# DIS07050H-V2_0-20231201.net
KiCad netlist of a schematic drawn in EAGLE
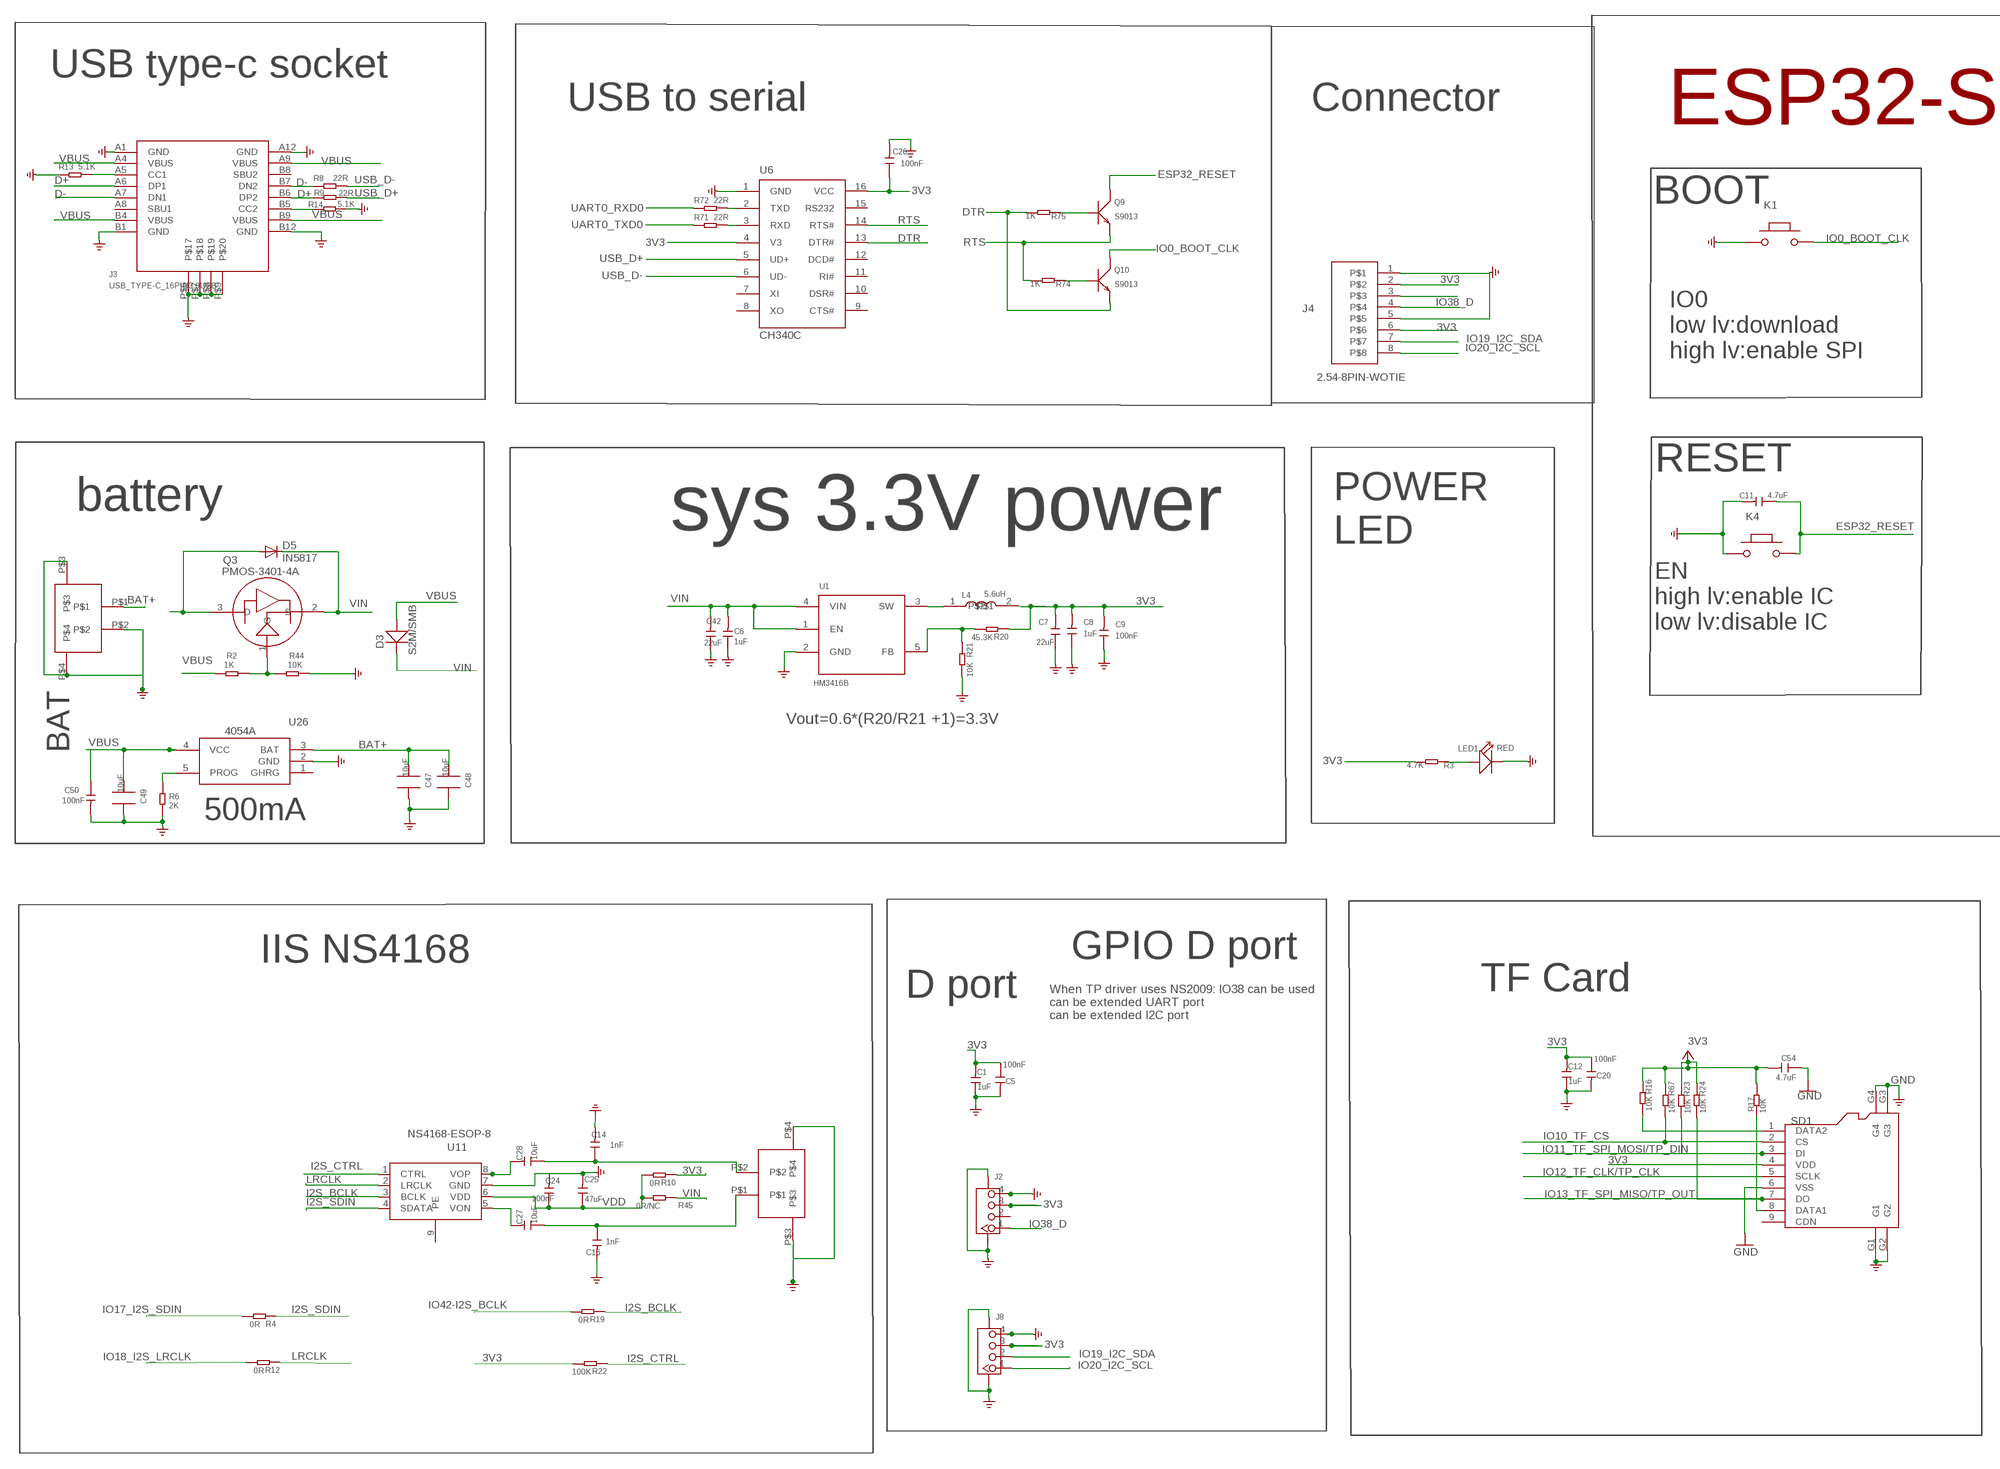
[diagram p0: schematic, sheet 1, part 1 of 2]
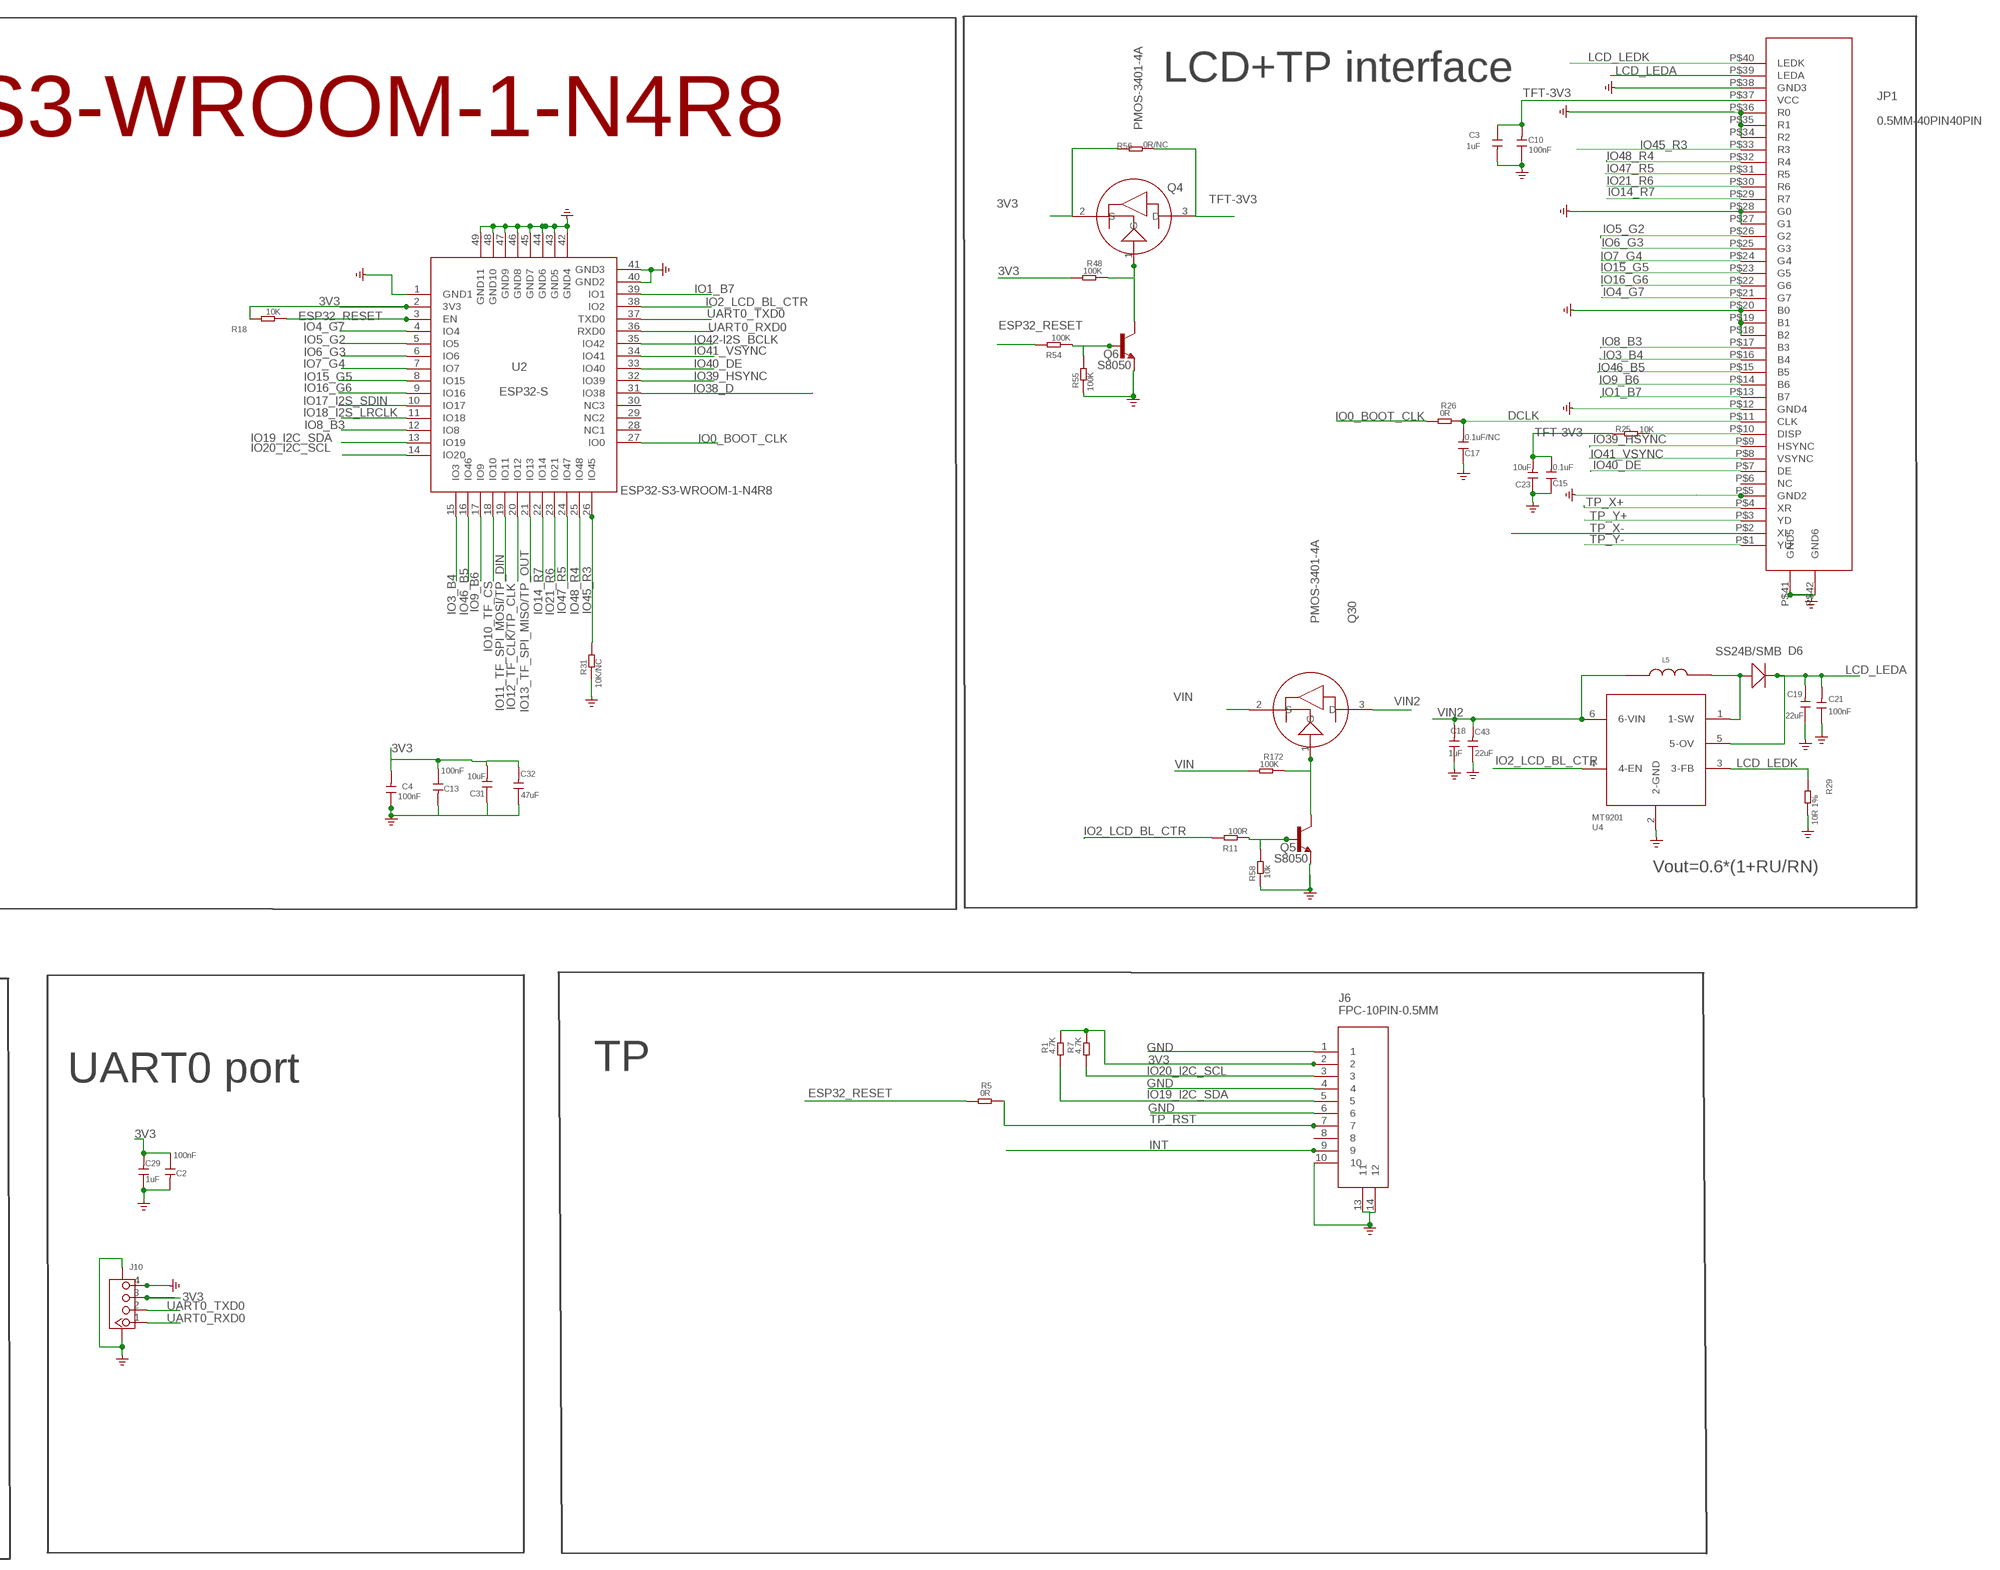
[diagram p1: schematic, sheet 1, part 2 of 2]

(export (version "E")
  (design (tool "Eeschema 10.0.6"))
  (components
    (comp (ref "C1")
      (value "1uF")
      (footprint "eagle-import:DISCRETE_C0603")
      (libsource (lib "eagle-import") (part "A_xbj_DISCRETE_C-0603"))
    )
    (comp (ref "C2")
      (value "100nF")
      (footprint "eagle-import:C0603")
      (libsource (lib "eagle-import") (part "C-0603"))
    )
    (comp (ref "C3")
      (value "1uF")
      (footprint "eagle-import:C0603")
      (libsource (lib "eagle-import") (part "C-0603"))
    )
    (comp (ref "C4")
      (value "100nF")
      (footprint "eagle-import:C0603")
      (libsource (lib "eagle-import") (part "C-0603"))
    )
    (comp (ref "C5")
      (value "100nF")
      (footprint "eagle-import:C0603")
      (libsource (lib "eagle-import") (part "C-0603"))
    )
    (comp (ref "C6")
      (value "1uF")
      (footprint "eagle-import:0603")
      (libsource (lib "eagle-import") (part "C0603"))
    )
    (comp (ref "C7")
      (value "22uF")
      (footprint "eagle-import:0805")
      (libsource (lib "eagle-import") (part "C0805"))
    )
    (comp (ref "C8")
      (value "1uF")
      (footprint "eagle-import:0603")
      (libsource (lib "eagle-import") (part "C0603"))
    )
    (comp (ref "C9")
      (value "100nF")
      (footprint "eagle-import:0603")
      (libsource (lib "eagle-import") (part "C0603"))
    )
    (comp (ref "C10")
      (value "100nF")
      (footprint "eagle-import:C0603")
      (libsource (lib "eagle-import") (part "C-0603"))
    )
    (comp (ref "C11")
      (value "4.7uF")
      (footprint "eagle-import:0603")
      (libsource (lib "eagle-import") (part "C0603"))
    )
    (comp (ref "C12")
      (value "1uF")
      (footprint "eagle-import:DISCRETE_C0603")
      (libsource (lib "eagle-import") (part "A_xbj_DISCRETE_C-0603"))
    )
    (comp (ref "C13")
      (value "100nF")
      (footprint "eagle-import:C0603")
      (libsource (lib "eagle-import") (part "C-0603"))
    )
    (comp (ref "C14")
      (value "1nF")
      (footprint "eagle-import:C0603")
      (libsource (lib "eagle-import") (part "C-0603"))
    )
    (comp (ref "C15")
      (value "0.1uF")
      (footprint "eagle-import:DISCRETE_C0603")
      (libsource (lib "eagle-import") (part "DISCRETE_C-0603"))
    )
    (comp (ref "C16")
      (value "1nF")
      (footprint "eagle-import:C0603")
      (libsource (lib "eagle-import") (part "C-0603"))
    )
    (comp (ref "C17")
      (value "0.1uF/NC")
      (footprint "eagle-import:DISCRETE_C0603")
      (libsource (lib "eagle-import") (part "DISCRETE_C-0603"))
    )
    (comp (ref "C18")
      (value "1uF")
      (footprint "eagle-import:0603")
      (libsource (lib "eagle-import") (part "C0603"))
    )
    (comp (ref "C19")
      (value "22uF")
      (footprint "eagle-import:0805")
      (libsource (lib "eagle-import") (part "C0805"))
    )
    (comp (ref "C20")
      (value "100nF")
      (footprint "eagle-import:C0603")
      (libsource (lib "eagle-import") (part "C-0603"))
    )
    (comp (ref "C21")
      (value "100nF")
      (footprint "eagle-import:0603")
      (libsource (lib "eagle-import") (part "C0603"))
    )
    (comp (ref "C23")
      (value "10uF")
      (footprint "eagle-import:DISCRETE_C0603")
      (libsource (lib "eagle-import") (part "DISCRETE_C-0603"))
    )
    (comp (ref "C24")
      (value "100nF")
      (footprint "eagle-import:C0603")
      (libsource (lib "eagle-import") (part "C-0603"))
    )
    (comp (ref "C25")
      (value "47uF")
      (footprint "eagle-import:0805")
      (libsource (lib "eagle-import") (part "C0805"))
    )
    (comp (ref "C26")
      (value "100nF")
      (footprint "eagle-import:0603")
      (libsource (lib "eagle-import") (part "C0603"))
    )
    (comp (ref "C27")
      (value "10uF")
      (footprint "eagle-import:DISCRETE_C0603")
      (libsource (lib "eagle-import") (part "A_xbj_DISCRETE_C-0603"))
    )
    (comp (ref "C28")
      (value "10uF")
      (footprint "eagle-import:DISCRETE_C0603")
      (libsource (lib "eagle-import") (part "A_xbj_DISCRETE_C-0603"))
    )
    (comp (ref "C29")
      (value "1uF")
      (footprint "eagle-import:DISCRETE_C0603")
      (libsource (lib "eagle-import") (part "A_xbj_DISCRETE_C-0603"))
    )
    (comp (ref "C31")
      (value "10uF")
      (footprint "eagle-import:DISCRETE_C0603")
      (libsource (lib "eagle-import") (part "DISCRETE_C-0603"))
    )
    (comp (ref "C32")
      (value "47uF")
      (footprint "eagle-import:0805")
      (libsource (lib "eagle-import") (part "C0805"))
    )
    (comp (ref "C42")
      (value "22uF")
      (footprint "eagle-import:0805")
      (libsource (lib "eagle-import") (part "C0805"))
    )
    (comp (ref "C43")
      (value "22uF")
      (footprint "eagle-import:0805")
      (libsource (lib "eagle-import") (part "C0805"))
    )
    (comp (ref "C47")
      (value "10uF")
      (footprint "eagle-import:0805_S")
      (libsource (lib "eagle-import") (part "C0805_S"))
    )
    (comp (ref "C48")
      (value "10uF")
      (footprint "eagle-import:0805_S")
      (libsource (lib "eagle-import") (part "C0805_S"))
    )
    (comp (ref "C49")
      (value "10uF")
      (footprint "eagle-import:0805_S")
      (libsource (lib "eagle-import") (part "C0805_S"))
    )
    (comp (ref "C50")
      (value "100nF")
      (footprint "eagle-import:C0603")
      (libsource (lib "eagle-import") (part "C-0603"))
    )
    (comp (ref "C54")
      (value "4.7uF")
      (footprint "eagle-import:DISCRETE_C0603")
      (libsource (lib "eagle-import") (part "DISCRETE_C-0603"))
    )
    (comp (ref "D3")
      (value "S2M/SMB")
      (footprint "eagle-import:214AB")
      (libsource (lib "eagle-import") (part "214ABDO-214AB"))
    )
    (comp (ref "D5")
      (value "IN5817")
      (footprint "eagle-import:DO-214AC")
      (libsource (lib "eagle-import") (part "DIODE-DO-214AC"))
    )
    (comp (ref "D6")
      (value "SS24B/SMB")
      (footprint "eagle-import:214AB")
      (libsource (lib "eagle-import") (part "214ABDO-214AB"))
    )
    (comp (ref "J1")
      (value "PH2.0WT-2PIN")
      (footprint "eagle-import:PH2.0WT-2PIN")
      (libsource (lib "eagle-import") (part "PH2.0WT-2PIN"))
    )
    (comp (ref "J2")
      (value "CONNECTOR_TWIG-4P-2.0-SMD-FEMALE-REINFORCE90D")
      (footprint "eagle-import:CONNECTOR_4P-SMD-2.0-90D")
      (libsource (lib "eagle-import") (part "CONNECTOR_TWIG-4P-2.0-SMD-FEMALE-REINFORCE90D"))
    )
    (comp (ref "J3")
      (value "USB_TYPE-C_16PIN3.0USB")
      (footprint "eagle-import:KEVIN_3.0TYPEC-SMD")
      (libsource (lib "eagle-import") (part "USB_TYPE-C_16PIN3.0USB"))
    )
    (comp (ref "J4")
      (value "2.54-8PIN-WOTIE")
      (footprint "eagle-import:2.54-8P-WOTIE")
      (libsource (lib "eagle-import") (part "2.54-8PIN-WOTIE"))
    )
    (comp (ref "J5")
      (value "PH2.0WT-2PIN")
      (footprint "eagle-import:PH2.0WT-2PIN")
      (libsource (lib "eagle-import") (part "PH2.0WT-2PIN"))
    )
    (comp (ref "J6")
      (value "FPC-10PIN-0.5MM")
      (footprint "eagle-import:FPC-10PIN-0.5MM")
      (libsource (lib "eagle-import") (part "FPC-10PIN-0.5MM"))
    )
    (comp (ref "J8")
      (value "CONNECTOR_TWIG-4P-2.0-SMD-FEMALE-REINFORCE90D")
      (footprint "eagle-import:CONNECTOR_4P-SMD-2.0-90D")
      (libsource (lib "eagle-import") (part "CONNECTOR_TWIG-4P-2.0-SMD-FEMALE-REINFORCE90D"))
    )
    (comp (ref "J10")
      (value "CONNECTOR_TWIG-4P-2.0-SMD-FEMALE-REINFORCE90D")
      (footprint "eagle-import:CONNECTOR_4P-SMD-2.0-90D")
      (libsource (lib "eagle-import") (part "CONNECTOR_TWIG-4P-2.0-SMD-FEMALE-REINFORCE90D"))
    )
    (comp (ref "JP1")
      (value "0.5MM-40PIN40PIN")
      (footprint "eagle-import:0.5MM_40P")
      (libsource (lib "eagle-import") (part "0.5MM-40PIN40PIN"))
    )
    (comp (ref "K1")
      (value "BUTTON")
      (footprint "eagle-import:157SW")
      (libsource (lib "eagle-import") (part "PB157"))
    )
    (comp (ref "K4")
      (value "BUTTON")
      (footprint "eagle-import:157SW")
      (libsource (lib "eagle-import") (part "PB157"))
    )
    (comp (ref "L4")
      (value "5.6uH")
      (footprint "eagle-import:CD54_CD54")
      (libsource (lib "eagle-import") (part "L-0530"))
    )
    (comp (ref "L5")
      (value "CD32_6.8uH")
      (footprint "eagle-import:CD32")
      (libsource (lib "eagle-import") (part "CD32_950MA"))
    )
    (comp (ref "LED1")
      (value "RED")
      (footprint "eagle-import:DISCRETE_LED-0603")
      (libsource (lib "eagle-import") (part "DISCRETE_LED0603"))
    )
    (comp (ref "Q3")
      (value "PMOS-3401-4A")
      (footprint "eagle-import:SOT-23")
      (libsource (lib "eagle-import") (part "P-MOS-SOT23"))
    )
    (comp (ref "Q4")
      (value "PMOS-3401-4A")
      (footprint "eagle-import:SOT-23")
      (libsource (lib "eagle-import") (part "P-MOS-SOT23"))
    )
    (comp (ref "Q5")
      (value "S8050")
      (footprint "eagle-import:SPARKFUN_SOT23")
      (libsource (lib "eagle-import") (part "SPARKFUN_TRANSISTOR_NPNSOT23"))
    )
    (comp (ref "Q6")
      (value "S8050")
      (footprint "eagle-import:SPARKFUN_SOT23")
      (libsource (lib "eagle-import") (part "SPARKFUN_TRANSISTOR_NPNSOT23"))
    )
    (comp (ref "Q9")
      (value "S9013")
      (footprint "eagle-import:SOT23@1")
      (libsource (lib "eagle-import") (part "TRANSISTOR-NPN-SOT23"))
    )
    (comp (ref "Q10")
      (value "S9013")
      (footprint "eagle-import:SOT23@1")
      (libsource (lib "eagle-import") (part "TRANSISTOR-NPN-SOT23"))
    )
    (comp (ref "Q30")
      (value "PMOS-3401-4A")
      (footprint "eagle-import:SOT-23")
      (libsource (lib "eagle-import") (part "P-MOS-SOT23"))
    )
    (comp (ref "R1")
      (value "4.7K")
      (footprint "eagle-import:R0603")
      (libsource (lib "eagle-import") (part "R-0603"))
    )
    (comp (ref "R2")
      (value "1K")
      (footprint "eagle-import:DISCRETE_R0603")
      (libsource (lib "eagle-import") (part "DISCRETE_R-0603"))
    )
    (comp (ref "R3")
      (value "4.7K")
      (footprint "eagle-import:DISCRETE_R0603")
      (libsource (lib "eagle-import") (part "Crowtail-_LED-V2.0-20190615-01_DISCRETE_R-0603"))
    )
    (comp (ref "R4")
      (value "0R")
      (footprint "eagle-import:DISCRETE_R0603")
      (libsource (lib "eagle-import") (part "Crowtail-_LED-V2.0-20190615-01_DISCRETE_R-0603"))
    )
    (comp (ref "R5")
      (value "0R")
      (footprint "eagle-import:R0603")
      (libsource (lib "eagle-import") (part "R-0603"))
    )
    (comp (ref "R6")
      (value "2K")
      (footprint "eagle-import:DISCRETE_R0603")
      (libsource (lib "eagle-import") (part "DISCRETE_R-0603"))
    )
    (comp (ref "R7")
      (value "4.7K")
      (footprint "eagle-import:R0603")
      (libsource (lib "eagle-import") (part "R-0603"))
    )
    (comp (ref "R8")
      (value "22R")
      (footprint "eagle-import:DISCRETE_R0603")
      (libsource (lib "eagle-import") (part "Crowtail-_LED-V2.0-20190615-01_DISCRETE_R-0603"))
    )
    (comp (ref "R9")
      (value "22R")
      (footprint "eagle-import:DISCRETE_R0603")
      (libsource (lib "eagle-import") (part "Crowtail-_LED-V2.0-20190615-01_DISCRETE_R-0603"))
    )
    (comp (ref "R10")
      (value "0R")
      (footprint "eagle-import:DISCRETE_R0603")
      (libsource (lib "eagle-import") (part "Crowtail-_LED-V2.0-20190615-01_DISCRETE_R-0603"))
    )
    (comp (ref "R11")
      (value "100R")
      (footprint "eagle-import:R0603")
      (libsource (lib "eagle-import") (part "R0603"))
    )
    (comp (ref "R12")
      (value "0R")
      (footprint "eagle-import:DISCRETE_R0603")
      (libsource (lib "eagle-import") (part "Crowtail-_LED-V2.0-20190615-01_DISCRETE_R-0603"))
    )
    (comp (ref "R13")
      (value "5.1K")
      (footprint "eagle-import:DISCRETE_R0603")
      (libsource (lib "eagle-import") (part "Crowtail-_LED-V2.0-20190615-01_DISCRETE_R-0603"))
    )
    (comp (ref "R14")
      (value "5.1K")
      (footprint "eagle-import:DISCRETE_R0603")
      (libsource (lib "eagle-import") (part "Crowtail-_LED-V2.0-20190615-01_DISCRETE_R-0603"))
    )
    (comp (ref "R16")
      (value "10K")
      (footprint "eagle-import:DISCRETE_R0603")
      (libsource (lib "eagle-import") (part "Crowtail-_LED-V2.0-20190615-01_DISCRETE_R-0603"))
    )
    (comp (ref "R17")
      (value "10K")
      (footprint "eagle-import:DISCRETE_R0603")
      (libsource (lib "eagle-import") (part "Crowtail-_LED-V2.0-20190615-01_DISCRETE_R-0603"))
    )
    (comp (ref "R18")
      (value "10K")
      (footprint "eagle-import:DISCRETE_R0603")
      (libsource (lib "eagle-import") (part "Crowtail-_LED-V2.0-20190615-01_DISCRETE_R-0603"))
    )
    (comp (ref "R19")
      (value "0R")
      (footprint "eagle-import:DISCRETE_R0603")
      (libsource (lib "eagle-import") (part "Crowtail-_LED-V2.0-20190615-01_DISCRETE_R-0603"))
    )
    (comp (ref "R20")
      (value "45.3K")
      (footprint "eagle-import:DISCRETE_R0603")
      (libsource (lib "eagle-import") (part "Crowtail-_LED-V2.0-20190615-01_DISCRETE_R-0603"))
    )
    (comp (ref "R21")
      (value "10K")
      (footprint "eagle-import:DISCRETE_R0603")
      (libsource (lib "eagle-import") (part "Crowtail-_LED-V2.0-20190615-01_DISCRETE_R-0603"))
    )
    (comp (ref "R22")
      (value "100K")
      (footprint "eagle-import:DISCRETE_R0603")
      (libsource (lib "eagle-import") (part "Crowtail-_LED-V2.0-20190615-01_DISCRETE_R-0603"))
    )
    (comp (ref "R23")
      (value "10K")
      (footprint "eagle-import:DISCRETE_R0603")
      (libsource (lib "eagle-import") (part "Crowtail-_LED-V2.0-20190615-01_DISCRETE_R-0603"))
    )
    (comp (ref "R24")
      (value "10K")
      (footprint "eagle-import:DISCRETE_R0603")
      (libsource (lib "eagle-import") (part "Crowtail-_LED-V2.0-20190615-01_DISCRETE_R-0603"))
    )
    (comp (ref "R25")
      (value "10K")
      (footprint "eagle-import:DISCRETE_R0603")
      (libsource (lib "eagle-import") (part "Crowtail-_LED-V2.0-20190615-01_DISCRETE_R-0603"))
    )
    (comp (ref "R26")
      (value "0R")
      (footprint "eagle-import:R0603")
      (libsource (lib "eagle-import") (part "R-0603"))
    )
    (comp (ref "R29")
      (value "10R 1%")
      (footprint "eagle-import:DISCRETE_R0603")
      (libsource (lib "eagle-import") (part "Crowtail-_LED-V2.0-20190615-01_DISCRETE_R-0603"))
    )
    (comp (ref "R31")
      (value "10K/NC")
      (footprint "eagle-import:R0603")
      (libsource (lib "eagle-import") (part "R0603"))
    )
    (comp (ref "R44")
      (value "10K")
      (footprint "eagle-import:DISCRETE_R0603")
      (libsource (lib "eagle-import") (part "DISCRETE_R-0603"))
    )
    (comp (ref "R45")
      (value "0R/NC")
      (footprint "eagle-import:DISCRETE_R0603")
      (libsource (lib "eagle-import") (part "Crowtail-_LED-V2.0-20190615-01_DISCRETE_R-0603"))
    )
    (comp (ref "R48")
      (value "100K")
      (footprint "eagle-import:R0603")
      (libsource (lib "eagle-import") (part "R-0603"))
    )
    (comp (ref "R54")
      (value "100K")
      (footprint "eagle-import:R0603")
      (libsource (lib "eagle-import") (part "R0603"))
    )
    (comp (ref "R55")
      (value "100K")
      (footprint "eagle-import:R0603")
      (libsource (lib "eagle-import") (part "R0603"))
    )
    (comp (ref "R56")
      (value "0R/NC")
      (footprint "eagle-import:DISCRETE_R0603")
      (libsource (lib "eagle-import") (part "Crowtail-_LED-V2.0-20190615-01_DISCRETE_R-0603"))
    )
    (comp (ref "R58")
      (value "10k")
      (footprint "eagle-import:R0603")
      (libsource (lib "eagle-import") (part "R0603"))
    )
    (comp (ref "R67")
      (value "10K")
      (footprint "eagle-import:DISCRETE_R0603")
      (libsource (lib "eagle-import") (part "Crowtail-_LED-V2.0-20190615-01_DISCRETE_R-0603"))
    )
    (comp (ref "R71")
      (value "22R")
      (footprint "eagle-import:DISCRETE_R0603")
      (libsource (lib "eagle-import") (part "Crowtail-_LED-V2.0-20190615-01_DISCRETE_R-0603"))
    )
    (comp (ref "R72")
      (value "22R")
      (footprint "eagle-import:DISCRETE_R0603")
      (libsource (lib "eagle-import") (part "Crowtail-_LED-V2.0-20190615-01_DISCRETE_R-0603"))
    )
    (comp (ref "R74")
      (value "1K")
      (footprint "eagle-import:DISCRETE_R0603")
      (libsource (lib "eagle-import") (part "Crowtail-_LED-V2.0-20190615-01_DISCRETE_R-0603"))
    )
    (comp (ref "R75")
      (value "1K")
      (footprint "eagle-import:DISCRETE_R0603")
      (libsource (lib "eagle-import") (part "Crowtail-_LED-V2.0-20190615-01_DISCRETE_R-0603"))
    )
    (comp (ref "R172")
      (value "100K")
      (footprint "eagle-import:R0603")
      (libsource (lib "eagle-import") (part "R-0603"))
    )
    (comp (ref "SD1")
      (value "HOLDER-MICROSD-9P")
      (footprint "eagle-import:9P-SMD-W_-RING")
      (libsource (lib "eagle-import") (part "HOLDER-MICROSD-9P"))
    )
    (comp (ref "U1")
      (value "HM3416B")
      (footprint "eagle-import:A_XBJ_SOT23-5")
      (libsource (lib "eagle-import") (part "A_XBJ_HM3420B"))
    )
    (comp (ref "U2")
      (value "ESP32-S")
      (footprint "eagle-import:ESP32-S3")
      (fields (field (name "U2") "ESP32-S3-WROOM-1-N4R8"))
      (libsource (lib "eagle-import") (part "ESP32-S"))
    )
    (comp (ref "U4")
      (value "MT9201")
      (footprint "eagle-import:SOT23-6")
      (libsource (lib "eagle-import") (part "MT9201"))
    )
    (comp (ref "U6")
      (value "CH340C")
      (footprint "eagle-import:SOP-16")
      (libsource (lib "eagle-import") (part "CH340G"))
    )
    (comp (ref "U11")
      (value "NS4168-ESOP-8")
      (footprint "eagle-import:NS4168-ESOP-8")
      (libsource (lib "eagle-import") (part "NS4168-ESOP-8"))
    )
    (comp (ref "U26")
      (value "4054A")
      (footprint "eagle-import:SOP23-5")
      (libsource (lib "eagle-import") (part "4054A"))
    )
  )
  (nets
    (net (code "1") (name "+3V3") (class "Default")
      (node (ref "C1") (pin "2") (pinfunction "2_2") (pintype "passive"))
      (node (ref "C12") (pin "2") (pinfunction "2_2") (pintype "passive"))
      (node (ref "C13") (pin "1") (pinfunction "1_1") (pintype "passive"))
      (node (ref "C2") (pin "1") (pinfunction "1_1") (pintype "passive"))
      (node (ref "C20") (pin "1") (pinfunction "1_1") (pintype "passive"))
      (node (ref "C26") (pin "1") (pinfunction "1_1") (pintype "passive"))
      (node (ref "C29") (pin "2") (pinfunction "2_2") (pintype "passive"))
      (node (ref "C31") (pin "2") (pinfunction "2_2") (pintype "passive"))
      (node (ref "C32") (pin "2") (pinfunction "2_2") (pintype "passive"))
      (node (ref "C4") (pin "2") (pinfunction "2_2") (pintype "passive"))
      (node (ref "C5") (pin "1") (pinfunction "1_1") (pintype "passive"))
      (node (ref "C54") (pin "2") (pinfunction "2_2") (pintype "passive"))
      (node (ref "C7") (pin "2") (pinfunction "2_2") (pintype "passive"))
      (node (ref "C8") (pin "2") (pinfunction "2_2") (pintype "passive"))
      (node (ref "C9") (pin "2") (pinfunction "2_2") (pintype "passive"))
      (node (ref "J10") (pin "3") (pinfunction "3_3") (pintype "bidirectional"))
      (node (ref "J2") (pin "3") (pinfunction "3_3") (pintype "bidirectional"))
      (node (ref "J4") (pin "2") (pinfunction "P$2_2") (pintype "bidirectional"))
      (node (ref "J4") (pin "6") (pinfunction "P$6_6") (pintype "bidirectional"))
      (node (ref "J6") (pin "2") (pinfunction "2_2") (pintype "bidirectional"))
      (node (ref "J8") (pin "3") (pinfunction "3_3") (pintype "bidirectional"))
      (node (ref "L4") (pin "2") (pinfunction "P$2_2") (pintype "bidirectional"))
      (node (ref "Q4") (pin "2") (pinfunction "S_2") (pintype "bidirectional"))
      (node (ref "R1") (pin "2") (pinfunction "2_2") (pintype "passive"))
      (node (ref "R10") (pin "1") (pinfunction "1_1") (pintype "passive"))
      (node (ref "R16") (pin "1") (pinfunction "1_1") (pintype "passive"))
      (node (ref "R17") (pin "1") (pinfunction "1_1") (pintype "passive"))
      (node (ref "R18") (pin "1") (pinfunction "1_1") (pintype "passive"))
      (node (ref "R20") (pin "1") (pinfunction "1_1") (pintype "passive"))
      (node (ref "R22") (pin "2") (pinfunction "2_2") (pintype "passive"))
      (node (ref "R23") (pin "1") (pinfunction "1_1") (pintype "passive"))
      (node (ref "R24") (pin "1") (pinfunction "1_1") (pintype "passive"))
      (node (ref "R3") (pin "2") (pinfunction "2_2") (pintype "passive"))
      (node (ref "R48") (pin "1") (pinfunction "1_1") (pintype "passive"))
      (node (ref "R56") (pin "1") (pinfunction "1_1") (pintype "passive"))
      (node (ref "R67") (pin "1") (pinfunction "1_1") (pintype "passive"))
      (node (ref "R7") (pin "2") (pinfunction "2_2") (pintype "passive"))
      (node (ref "SD1") (pin "4") (pinfunction "VDD_4") (pintype "bidirectional"))
      (node (ref "U2") (pin "2") (pinfunction "3V3_2") (pintype "bidirectional"))
      (node (ref "U6") (pin "16") (pinfunction "VCC_16") (pintype "bidirectional"))
      (node (ref "U6") (pin "4") (pinfunction "V3_4") (pintype "bidirectional"))
    )
    (net (code "2") (name "/BAT+") (class "Default")
      (node (ref "C47") (pin "2") (pinfunction "2_2") (pintype "bidirectional"))
      (node (ref "C48") (pin "2") (pinfunction "2_2") (pintype "bidirectional"))
      (node (ref "D5") (pin "A") (pinfunction "A_A") (pintype "passive"))
      (node (ref "J1") (pin "P$1") (pinfunction "P$1_P$1") (pintype "bidirectional"))
      (node (ref "Q3") (pin "3") (pinfunction "D_3") (pintype "bidirectional"))
      (node (ref "U26") (pin "3") (pinfunction "BAT_3") (pintype "bidirectional"))
    )
    (net (code "3") (name "/D+") (class "Default")
      (node (ref "J3") (pin "A6") (pinfunction "DP1_A6") (pintype "bidirectional"))
      (node (ref "J3") (pin "B6") (pinfunction "DP2_B6") (pintype "bidirectional"))
      (node (ref "R9") (pin "1") (pinfunction "1_1") (pintype "passive"))
    )
    (net (code "4") (name "/D-") (class "Default")
      (node (ref "J3") (pin "A7") (pinfunction "DN1_A7") (pintype "bidirectional"))
      (node (ref "J3") (pin "B7") (pinfunction "DN2_B7") (pintype "bidirectional"))
      (node (ref "R8") (pin "1") (pinfunction "1_1") (pintype "passive"))
    )
    (net (code "5") (name "/DCLK") (class "Default")
      (node (ref "C17") (pin "2") (pinfunction "2_2") (pintype "passive"))
      (node (ref "JP1") (pin "P$11") (pinfunction "CLK_P$11") (pintype "bidirectional"))
      (node (ref "R26") (pin "2") (pinfunction "2_2") (pintype "passive"))
    )
    (net (code "6") (name "/DTR") (class "Default")
      (node (ref "Q10") (pin "2") (pinfunction "E_2") (pintype "passive"))
      (node (ref "R75") (pin "2") (pinfunction "2_2") (pintype "passive"))
      (node (ref "U6") (pin "13") (pinfunction "DTR#_13") (pintype "bidirectional"))
    )
    (net (code "7") (name "/ESP32_RESET") (class "Default")
      (node (ref "C11") (pin "1") (pinfunction "1_1") (pintype "passive"))
      (node (ref "K4") (pin "2") (pinfunction "2_2") (pintype "passive"))
      (node (ref "Q9") (pin "3") (pinfunction "C_3") (pintype "passive"))
      (node (ref "R18") (pin "2") (pinfunction "2_2") (pintype "passive"))
      (node (ref "R5") (pin "1") (pinfunction "1_1") (pintype "passive"))
      (node (ref "R54") (pin "2") (pinfunction "2_2") (pintype "passive"))
      (node (ref "U2") (pin "3") (pinfunction "EN_3") (pintype "bidirectional"))
    )
    (net (code "8") (name "/I2S_BCLK") (class "Default")
      (node (ref "R19") (pin "1") (pinfunction "1_1") (pintype "passive"))
      (node (ref "U11") (pin "3") (pinfunction "BCLK_3") (pintype "bidirectional"))
    )
    (net (code "9") (name "/I2S_CTRL") (class "Default")
      (node (ref "R22") (pin "1") (pinfunction "1_1") (pintype "passive"))
      (node (ref "U11") (pin "1") (pinfunction "CTRL_1") (pintype "bidirectional"))
    )
    (net (code "10") (name "/I2S_SDIN") (class "Default")
      (node (ref "R4") (pin "1") (pinfunction "1_1") (pintype "passive"))
      (node (ref "U11") (pin "4") (pinfunction "SDATA_4") (pintype "bidirectional"))
    )
    (net (code "11") (name "/INT") (class "Default")
      (node (ref "J6") (pin "9") (pinfunction "9_9") (pintype "bidirectional"))
    )
    (net (code "12") (name "/IO0_BOOT_CLK") (class "Default")
      (node (ref "K1") (pin "2") (pinfunction "2_2") (pintype "passive"))
      (node (ref "Q10") (pin "3") (pinfunction "C_3") (pintype "passive"))
      (node (ref "R26") (pin "1") (pinfunction "1_1") (pintype "passive"))
      (node (ref "U2") (pin "27") (pinfunction "IO0_27") (pintype "bidirectional"))
    )
    (net (code "13") (name "/IO1_B7") (class "Default")
      (node (ref "JP1") (pin "P$13") (pinfunction "B7_P$13") (pintype "bidirectional"))
      (node (ref "U2") (pin "39") (pinfunction "IO1_39") (pintype "bidirectional"))
    )
    (net (code "14") (name "/IO2_LCD_BL_CTR") (class "Default")
      (node (ref "R11") (pin "2") (pinfunction "2_2") (pintype "passive"))
      (node (ref "U2") (pin "38") (pinfunction "IO2_38") (pintype "bidirectional"))
      (node (ref "U4") (pin "4") (pinfunction "4-EN_4") (pintype "bidirectional"))
    )
    (net (code "15") (name "/IO3_B4") (class "Default")
      (node (ref "JP1") (pin "P$16") (pinfunction "B4_P$16") (pintype "bidirectional"))
      (node (ref "U2") (pin "15") (pinfunction "IO3_15") (pintype "bidirectional"))
    )
    (net (code "16") (name "/IO4_G7") (class "Default")
      (node (ref "JP1") (pin "P$21") (pinfunction "G7_P$21") (pintype "bidirectional"))
      (node (ref "U2") (pin "4") (pinfunction "IO4_4") (pintype "bidirectional"))
    )
    (net (code "17") (name "/IO5_G2") (class "Default")
      (node (ref "JP1") (pin "P$26") (pinfunction "G2_P$26") (pintype "bidirectional"))
      (node (ref "U2") (pin "5") (pinfunction "IO5_5") (pintype "bidirectional"))
    )
    (net (code "18") (name "/IO6_G3") (class "Default")
      (node (ref "JP1") (pin "P$25") (pinfunction "G3_P$25") (pintype "bidirectional"))
      (node (ref "U2") (pin "6") (pinfunction "IO6_6") (pintype "bidirectional"))
    )
    (net (code "19") (name "/IO7_G4") (class "Default")
      (node (ref "JP1") (pin "P$24") (pinfunction "G4_P$24") (pintype "bidirectional"))
      (node (ref "U2") (pin "7") (pinfunction "IO7_7") (pintype "bidirectional"))
    )
    (net (code "20") (name "/IO8_B3") (class "Default")
      (node (ref "JP1") (pin "P$17") (pinfunction "B3_P$17") (pintype "bidirectional"))
      (node (ref "U2") (pin "12") (pinfunction "IO8_12") (pintype "bidirectional"))
    )
    (net (code "21") (name "/IO9_B6") (class "Default")
      (node (ref "JP1") (pin "P$14") (pinfunction "B6_P$14") (pintype "bidirectional"))
      (node (ref "U2") (pin "17") (pinfunction "IO9_17") (pintype "bidirectional"))
    )
    (net (code "22") (name "/IO10_TF_CS") (class "Default")
      (node (ref "R67") (pin "2") (pinfunction "2_2") (pintype "passive"))
      (node (ref "SD1") (pin "2") (pinfunction "CS_2") (pintype "bidirectional"))
      (node (ref "U2") (pin "18") (pinfunction "IO10_18") (pintype "bidirectional"))
    )
    (net (code "23") (name "/IO11_TF_SPI_MOSI{slash}TP_DIN") (class "Default")
      (node (ref "R23") (pin "2") (pinfunction "2_2") (pintype "passive"))
      (node (ref "SD1") (pin "3") (pinfunction "DI_3") (pintype "bidirectional"))
      (node (ref "U2") (pin "19") (pinfunction "IO11_19") (pintype "bidirectional"))
    )
    (net (code "24") (name "/IO12_TF_CLK{slash}TP_CLK") (class "Default")
      (node (ref "SD1") (pin "5") (pinfunction "SCLK_5") (pintype "bidirectional"))
      (node (ref "U2") (pin "20") (pinfunction "IO12_20") (pintype "bidirectional"))
    )
    (net (code "25") (name "/IO13_TF_SPI_MISO{slash}TP_OUT") (class "Default")
      (node (ref "R24") (pin "2") (pinfunction "2_2") (pintype "passive"))
      (node (ref "SD1") (pin "7") (pinfunction "DO_7") (pintype "bidirectional"))
      (node (ref "U2") (pin "21") (pinfunction "IO13_21") (pintype "bidirectional"))
    )
    (net (code "26") (name "/IO14_R7") (class "Default")
      (node (ref "JP1") (pin "P$29") (pinfunction "R7_P$29") (pintype "bidirectional"))
      (node (ref "U2") (pin "22") (pinfunction "IO14_22") (pintype "bidirectional"))
    )
    (net (code "27") (name "/IO15_G5") (class "Default")
      (node (ref "JP1") (pin "P$23") (pinfunction "G5_P$23") (pintype "bidirectional"))
      (node (ref "U2") (pin "8") (pinfunction "IO15_8") (pintype "bidirectional"))
    )
    (net (code "28") (name "/IO16_G6") (class "Default")
      (node (ref "JP1") (pin "P$22") (pinfunction "G6_P$22") (pintype "bidirectional"))
      (node (ref "U2") (pin "9") (pinfunction "IO16_9") (pintype "bidirectional"))
    )
    (net (code "29") (name "/IO17_I2S_SDIN") (class "Default")
      (node (ref "R4") (pin "2") (pinfunction "2_2") (pintype "passive"))
      (node (ref "U2") (pin "10") (pinfunction "IO17_10") (pintype "bidirectional"))
    )
    (net (code "30") (name "/IO18_I2S_LRCLK") (class "Default")
      (node (ref "R12") (pin "2") (pinfunction "2_2") (pintype "passive"))
      (node (ref "U2") (pin "11") (pinfunction "IO18_11") (pintype "bidirectional"))
    )
    (net (code "31") (name "/IO19_I2C_SDA") (class "Default")
      (node (ref "J4") (pin "7") (pinfunction "P$7_7") (pintype "bidirectional"))
      (node (ref "J6") (pin "5") (pinfunction "5_5") (pintype "bidirectional"))
      (node (ref "J8") (pin "2") (pinfunction "2_2") (pintype "bidirectional"))
      (node (ref "R1") (pin "1") (pinfunction "1_1") (pintype "passive"))
      (node (ref "U2") (pin "13") (pinfunction "IO19_13") (pintype "bidirectional"))
    )
    (net (code "32") (name "/IO20_I2C_SCL") (class "Default")
      (node (ref "J4") (pin "8") (pinfunction "P$8_8") (pintype "bidirectional"))
      (node (ref "J6") (pin "3") (pinfunction "3_3") (pintype "bidirectional"))
      (node (ref "J8") (pin "1") (pinfunction "1_1") (pintype "bidirectional"))
      (node (ref "R7") (pin "1") (pinfunction "1_1") (pintype "passive"))
      (node (ref "U2") (pin "14") (pinfunction "IO20_14") (pintype "bidirectional"))
    )
    (net (code "33") (name "/IO21_R6") (class "Default")
      (node (ref "JP1") (pin "P$30") (pinfunction "R6_P$30") (pintype "bidirectional"))
      (node (ref "U2") (pin "23") (pinfunction "IO21_23") (pintype "bidirectional"))
    )
    (net (code "34") (name "/IO38_D") (class "Default")
      (node (ref "J2") (pin "1") (pinfunction "1_1") (pintype "bidirectional"))
      (node (ref "J4") (pin "4") (pinfunction "P$4_4") (pintype "bidirectional"))
      (node (ref "U2") (pin "31") (pinfunction "IO38_31") (pintype "bidirectional"))
    )
    (net (code "35") (name "/IO39_HSYNC") (class "Default")
      (node (ref "JP1") (pin "P$9") (pinfunction "HSYNC_P$9") (pintype "bidirectional"))
      (node (ref "U2") (pin "32") (pinfunction "IO39_32") (pintype "bidirectional"))
    )
    (net (code "36") (name "/IO40_DE") (class "Default")
      (node (ref "JP1") (pin "P$7") (pinfunction "DE_P$7") (pintype "bidirectional"))
      (node (ref "U2") (pin "33") (pinfunction "IO40_33") (pintype "bidirectional"))
    )
    (net (code "37") (name "/IO41_VSYNC") (class "Default")
      (node (ref "JP1") (pin "P$8") (pinfunction "VSYNC_P$8") (pintype "bidirectional"))
      (node (ref "U2") (pin "34") (pinfunction "IO41_34") (pintype "bidirectional"))
    )
    (net (code "38") (name "/IO42-I2S_BCLK") (class "Default")
      (node (ref "R19") (pin "2") (pinfunction "2_2") (pintype "passive"))
      (node (ref "U2") (pin "35") (pinfunction "IO42_35") (pintype "bidirectional"))
    )
    (net (code "39") (name "/IO45_R3") (class "Default")
      (node (ref "JP1") (pin "P$33") (pinfunction "R3_P$33") (pintype "bidirectional"))
      (node (ref "R31") (pin "2") (pinfunction "2_2") (pintype "passive"))
      (node (ref "U2") (pin "26") (pinfunction "IO45_26") (pintype "bidirectional"))
    )
    (net (code "40") (name "/IO46_B5") (class "Default")
      (node (ref "JP1") (pin "P$15") (pinfunction "B5_P$15") (pintype "bidirectional"))
      (node (ref "U2") (pin "16") (pinfunction "IO46_16") (pintype "bidirectional"))
    )
    (net (code "41") (name "/IO47_R5") (class "Default")
      (node (ref "JP1") (pin "P$31") (pinfunction "R5_P$31") (pintype "bidirectional"))
      (node (ref "U2") (pin "24") (pinfunction "IO47_24") (pintype "bidirectional"))
    )
    (net (code "42") (name "/IO48_R4") (class "Default")
      (node (ref "JP1") (pin "P$32") (pinfunction "R4_P$32") (pintype "bidirectional"))
      (node (ref "U2") (pin "25") (pinfunction "IO48_25") (pintype "bidirectional"))
    )
    (net (code "43") (name "/LCD_LEDA") (class "Default")
      (node (ref "C19") (pin "2") (pinfunction "2_2") (pintype "passive"))
      (node (ref "C21") (pin "2") (pinfunction "2_2") (pintype "passive"))
      (node (ref "D6") (pin "2") (pinfunction "-_2") (pintype "passive"))
      (node (ref "JP1") (pin "P$39") (pinfunction "LEDA_P$39") (pintype "bidirectional"))
      (node (ref "U4") (pin "5") (pinfunction "5-OV_5") (pintype "bidirectional"))
    )
    (net (code "44") (name "/LCD_LEDK") (class "Default")
      (node (ref "JP1") (pin "P$40") (pinfunction "LEDK_P$40") (pintype "bidirectional"))
      (node (ref "R29") (pin "1") (pinfunction "1_1") (pintype "passive"))
      (node (ref "U4") (pin "3") (pinfunction "3-FB_3") (pintype "bidirectional"))
    )
    (net (code "45") (name "/LRCLK") (class "Default")
      (node (ref "R12") (pin "1") (pinfunction "1_1") (pintype "passive"))
      (node (ref "U11") (pin "2") (pinfunction "LRCLK_2") (pintype "bidirectional"))
    )
    (net (code "46") (name "/RTS") (class "Default")
      (node (ref "Q9") (pin "2") (pinfunction "E_2") (pintype "passive"))
      (node (ref "R74") (pin "2") (pinfunction "2_2") (pintype "passive"))
      (node (ref "U6") (pin "14") (pinfunction "RTS#_14") (pintype "bidirectional"))
    )
    (net (code "47") (name "/TFT-3V3") (class "Default")
      (node (ref "C10") (pin "2") (pinfunction "2_2") (pintype "passive"))
      (node (ref "C15") (pin "2") (pinfunction "2_2") (pintype "passive"))
      (node (ref "C23") (pin "2") (pinfunction "2_2") (pintype "passive"))
      (node (ref "C3") (pin "1") (pinfunction "1_1") (pintype "passive"))
      (node (ref "JP1") (pin "P$37") (pinfunction "VCC_P$37") (pintype "bidirectional"))
      (node (ref "Q4") (pin "3") (pinfunction "D_3") (pintype "bidirectional"))
      (node (ref "R25") (pin "1") (pinfunction "1_1") (pintype "passive"))
      (node (ref "R56") (pin "2") (pinfunction "2_2") (pintype "passive"))
    )
    (net (code "48") (name "/TP_RST") (class "Default")
      (node (ref "J6") (pin "7") (pinfunction "7_7") (pintype "bidirectional"))
      (node (ref "R5") (pin "2") (pinfunction "2_2") (pintype "passive"))
    )
    (net (code "49") (name "/TP_X+") (class "Default")
      (node (ref "JP1") (pin "P$4") (pinfunction "XR_P$4") (pintype "bidirectional"))
    )
    (net (code "50") (name "/TP_X-") (class "Default")
      (node (ref "JP1") (pin "P$2") (pinfunction "XL_P$2") (pintype "bidirectional"))
    )
    (net (code "51") (name "/TP_Y+") (class "Default")
      (node (ref "JP1") (pin "P$3") (pinfunction "YD_P$3") (pintype "bidirectional"))
    )
    (net (code "52") (name "/TP_Y-") (class "Default")
      (node (ref "JP1") (pin "P$1") (pinfunction "YU_P$1") (pintype "bidirectional"))
    )
    (net (code "53") (name "/UART0_RXD0") (class "Default")
      (node (ref "J10") (pin "1") (pinfunction "1_1") (pintype "bidirectional"))
      (node (ref "R72") (pin "1") (pinfunction "1_1") (pintype "passive"))
      (node (ref "U2") (pin "36") (pinfunction "RXD0_36") (pintype "bidirectional"))
    )
    (net (code "54") (name "/UART0_TXD0") (class "Default")
      (node (ref "J10") (pin "2") (pinfunction "2_2") (pintype "bidirectional"))
      (node (ref "R71") (pin "1") (pinfunction "1_1") (pintype "passive"))
      (node (ref "U2") (pin "37") (pinfunction "TXD0_37") (pintype "bidirectional"))
    )
    (net (code "55") (name "/USB_D+") (class "Default")
      (node (ref "R9") (pin "2") (pinfunction "2_2") (pintype "passive"))
      (node (ref "U6") (pin "5") (pinfunction "UD+_5") (pintype "bidirectional"))
    )
    (net (code "56") (name "/USB_D-") (class "Default")
      (node (ref "R8") (pin "2") (pinfunction "2_2") (pintype "passive"))
      (node (ref "U6") (pin "6") (pinfunction "UD-_6") (pintype "bidirectional"))
    )
    (net (code "57") (name "/VBUS") (class "Default")
      (node (ref "C49") (pin "2") (pinfunction "2_2") (pintype "bidirectional"))
      (node (ref "C50") (pin "1") (pinfunction "1_1") (pintype "passive"))
      (node (ref "D3") (pin "1") (pinfunction "+_1") (pintype "passive"))
      (node (ref "J3") (pin "A4") (pinfunction "VBUS_A4") (pintype "bidirectional"))
      (node (ref "J3") (pin "A9") (pinfunction "VBUS_A9") (pintype "bidirectional"))
      (node (ref "J3") (pin "B4") (pinfunction "VBUS_B4") (pintype "bidirectional"))
      (node (ref "J3") (pin "B9") (pinfunction "VBUS_B9") (pintype "bidirectional"))
      (node (ref "R2") (pin "2") (pinfunction "2_2") (pintype "passive"))
      (node (ref "U26") (pin "4") (pinfunction "VCC_4") (pintype "bidirectional"))
    )
    (net (code "58") (name "/VDD") (class "Default")
      (node (ref "C24") (pin "1") (pinfunction "1_1") (pintype "passive"))
      (node (ref "C25") (pin "1") (pinfunction "1_1") (pintype "passive"))
      (node (ref "R10") (pin "2") (pinfunction "2_2") (pintype "passive"))
      (node (ref "R45") (pin "2") (pinfunction "2_2") (pintype "passive"))
      (node (ref "U11") (pin "6") (pinfunction "VDD_6") (pintype "bidirectional"))
    )
    (net (code "59") (name "/VIN") (class "Default")
      (node (ref "C42") (pin "2") (pinfunction "2_2") (pintype "passive"))
      (node (ref "C6") (pin "2") (pinfunction "2_2") (pintype "passive"))
      (node (ref "D3") (pin "2") (pinfunction "-_2") (pintype "passive"))
      (node (ref "D5") (pin "C") (pinfunction "C_C") (pintype "passive"))
      (node (ref "Q3") (pin "2") (pinfunction "S_2") (pintype "bidirectional"))
      (node (ref "Q30") (pin "2") (pinfunction "S_2") (pintype "bidirectional"))
      (node (ref "R172") (pin "1") (pinfunction "1_1") (pintype "passive"))
      (node (ref "R45") (pin "1") (pinfunction "1_1") (pintype "passive"))
      (node (ref "U1") (pin "1") (pinfunction "EN_1") (pintype "bidirectional"))
      (node (ref "U1") (pin "4") (pinfunction "VIN_4") (pintype "bidirectional"))
    )
    (net (code "60") (name "/VIN2") (class "Default")
      (node (ref "C18") (pin "2") (pinfunction "2_2") (pintype "passive"))
      (node (ref "C43") (pin "2") (pinfunction "2_2") (pintype "passive"))
      (node (ref "L5") (pin "1") (pinfunction "1_1") (pintype "bidirectional"))
      (node (ref "Q30") (pin "3") (pinfunction "D_3") (pintype "bidirectional"))
      (node (ref "U4") (pin "6") (pinfunction "6-VIN_6") (pintype "bidirectional"))
    )
    (net (code "61") (name "GND") (class "Default")
      (node (ref "C1") (pin "1") (pinfunction "1_1") (pintype "passive"))
      (node (ref "C10") (pin "1") (pinfunction "1_1") (pintype "passive"))
      (node (ref "C11") (pin "2") (pinfunction "2_2") (pintype "passive"))
      (node (ref "C12") (pin "1") (pinfunction "1_1") (pintype "passive"))
      (node (ref "C13") (pin "2") (pinfunction "2_2") (pintype "passive"))
      (node (ref "C14") (pin "2") (pinfunction "2_2") (pintype "passive"))
      (node (ref "C15") (pin "1") (pinfunction "1_1") (pintype "passive"))
      (node (ref "C16") (pin "2") (pinfunction "2_2") (pintype "passive"))
      (node (ref "C17") (pin "1") (pinfunction "1_1") (pintype "passive"))
      (node (ref "C18") (pin "1") (pinfunction "1_1") (pintype "passive"))
      (node (ref "C19") (pin "1") (pinfunction "1_1") (pintype "passive"))
      (node (ref "C2") (pin "2") (pinfunction "2_2") (pintype "passive"))
      (node (ref "C20") (pin "2") (pinfunction "2_2") (pintype "passive"))
      (node (ref "C21") (pin "1") (pinfunction "1_1") (pintype "passive"))
      (node (ref "C23") (pin "1") (pinfunction "1_1") (pintype "passive"))
      (node (ref "C24") (pin "2") (pinfunction "2_2") (pintype "passive"))
      (node (ref "C25") (pin "2") (pinfunction "2_2") (pintype "passive"))
      (node (ref "C26") (pin "2") (pinfunction "2_2") (pintype "passive"))
      (node (ref "C29") (pin "1") (pinfunction "1_1") (pintype "passive"))
      (node (ref "C3") (pin "2") (pinfunction "2_2") (pintype "passive"))
      (node (ref "C31") (pin "1") (pinfunction "1_1") (pintype "passive"))
      (node (ref "C32") (pin "1") (pinfunction "1_1") (pintype "passive"))
      (node (ref "C4") (pin "1") (pinfunction "1_1") (pintype "passive"))
      (node (ref "C42") (pin "1") (pinfunction "1_1") (pintype "passive"))
      (node (ref "C43") (pin "1") (pinfunction "1_1") (pintype "passive"))
      (node (ref "C47") (pin "1") (pinfunction "1_1") (pintype "bidirectional"))
      (node (ref "C48") (pin "1") (pinfunction "1_1") (pintype "bidirectional"))
      (node (ref "C49") (pin "1") (pinfunction "1_1") (pintype "bidirectional"))
      (node (ref "C5") (pin "2") (pinfunction "2_2") (pintype "passive"))
      (node (ref "C50") (pin "2") (pinfunction "2_2") (pintype "passive"))
      (node (ref "C54") (pin "1") (pinfunction "1_1") (pintype "passive"))
      (node (ref "C6") (pin "1") (pinfunction "1_1") (pintype "passive"))
      (node (ref "C7") (pin "1") (pinfunction "1_1") (pintype "passive"))
      (node (ref "C8") (pin "1") (pinfunction "1_1") (pintype "passive"))
      (node (ref "C9") (pin "1") (pinfunction "1_1") (pintype "passive"))
      (node (ref "J1") (pin "P$2") (pinfunction "P$2_P$2") (pintype "bidirectional"))
      (node (ref "J1") (pin "P$3") (pinfunction "P$3_P$3") (pintype "bidirectional"))
      (node (ref "J1") (pin "P$4") (pinfunction "P$4_P$4") (pintype "bidirectional"))
      (node (ref "J10") (pin "4") (pinfunction "4_4") (pintype "bidirectional"))
      (node (ref "J10") (pin "SS1") (pinfunction "SS1_SS1") (pintype "bidirectional"))
      (node (ref "J10") (pin "SS2") (pinfunction "SS2_SS2") (pintype "bidirectional"))
      (node (ref "J2") (pin "4") (pinfunction "4_4") (pintype "bidirectional"))
      (node (ref "J2") (pin "SS1") (pinfunction "SS1_SS1") (pintype "bidirectional"))
      (node (ref "J2") (pin "SS2") (pinfunction "SS2_SS2") (pintype "bidirectional"))
      (node (ref "J3") (pin "A1") (pinfunction "GND_A1") (pintype "bidirectional"))
      (node (ref "J3") (pin "A12") (pinfunction "GND_A12") (pintype "bidirectional"))
      (node (ref "J3") (pin "B1") (pinfunction "GND_B1") (pintype "bidirectional"))
      (node (ref "J3") (pin "B12") (pinfunction "GND_B12") (pintype "bidirectional"))
      (node (ref "J3") (pin "P$6") (pinfunction "P$17_P$6") (pintype "bidirectional"))
      (node (ref "J3") (pin "P$7") (pinfunction "P$18_P$7") (pintype "bidirectional"))
      (node (ref "J3") (pin "P$8") (pinfunction "P$19_P$8") (pintype "bidirectional"))
      (node (ref "J3") (pin "P$9") (pinfunction "P$20_P$9") (pintype "bidirectional"))
      (node (ref "J4") (pin "1") (pinfunction "P$1_1") (pintype "bidirectional"))
      (node (ref "J4") (pin "5") (pinfunction "P$5_5") (pintype "bidirectional"))
      (node (ref "J5") (pin "P$3") (pinfunction "P$3_P$3") (pintype "bidirectional"))
      (node (ref "J5") (pin "P$4") (pinfunction "P$4_P$4") (pintype "bidirectional"))
      (node (ref "J6") (pin "1") (pinfunction "1_1") (pintype "bidirectional"))
      (node (ref "J6") (pin "10") (pinfunction "10_10") (pintype "bidirectional"))
      (node (ref "J6") (pin "13") (pinfunction "11_13") (pintype "bidirectional"))
      (node (ref "J6") (pin "14") (pinfunction "12_14") (pintype "bidirectional"))
      (node (ref "J6") (pin "4") (pinfunction "4_4") (pintype "bidirectional"))
      (node (ref "J6") (pin "6") (pinfunction "6_6") (pintype "bidirectional"))
      (node (ref "J8") (pin "4") (pinfunction "4_4") (pintype "bidirectional"))
      (node (ref "J8") (pin "SS1") (pinfunction "SS1_SS1") (pintype "bidirectional"))
      (node (ref "J8") (pin "SS2") (pinfunction "SS2_SS2") (pintype "bidirectional"))
      (node (ref "JP1") (pin "P$12") (pinfunction "GND4_P$12") (pintype "bidirectional"))
      (node (ref "JP1") (pin "P$18") (pinfunction "B2_P$18") (pintype "bidirectional"))
      (node (ref "JP1") (pin "P$19") (pinfunction "B1_P$19") (pintype "bidirectional"))
      (node (ref "JP1") (pin "P$20") (pinfunction "B0_P$20") (pintype "bidirectional"))
      (node (ref "JP1") (pin "P$27") (pinfunction "G1_P$27") (pintype "bidirectional"))
      (node (ref "JP1") (pin "P$28") (pinfunction "G0_P$28") (pintype "bidirectional"))
      (node (ref "JP1") (pin "P$34") (pinfunction "R2_P$34") (pintype "bidirectional"))
      (node (ref "JP1") (pin "P$35") (pinfunction "R1_P$35") (pintype "bidirectional"))
      (node (ref "JP1") (pin "P$36") (pinfunction "R0_P$36") (pintype "bidirectional"))
      (node (ref "JP1") (pin "P$38") (pinfunction "GND3_P$38") (pintype "bidirectional"))
      (node (ref "JP1") (pin "P$41") (pinfunction "GND5_P$41") (pintype "bidirectional"))
      (node (ref "JP1") (pin "P$42") (pinfunction "GND6_P$42") (pintype "bidirectional"))
      (node (ref "JP1") (pin "P$5") (pinfunction "GND2_P$5") (pintype "bidirectional"))
      (node (ref "K1") (pin "1") (pinfunction "1_1") (pintype "passive"))
      (node (ref "K4") (pin "1") (pinfunction "1_1") (pintype "passive"))
      (node (ref "LED1") (pin "-") (pinfunction "-_-") (pintype "passive"))
      (node (ref "Q5") (pin "2") (pinfunction "E_2") (pintype "passive"))
      (node (ref "Q6") (pin "2") (pinfunction "E_2") (pintype "passive"))
      (node (ref "R13") (pin "1") (pinfunction "1_1") (pintype "passive"))
      (node (ref "R14") (pin "2") (pinfunction "2_2") (pintype "passive"))
      (node (ref "R21") (pin "2") (pinfunction "2_2") (pintype "passive"))
      (node (ref "R29") (pin "2") (pinfunction "2_2") (pintype "passive"))
      (node (ref "R31") (pin "1") (pinfunction "1_1") (pintype "passive"))
      (node (ref "R44") (pin "1") (pinfunction "1_1") (pintype "passive"))
      (node (ref "R55") (pin "1") (pinfunction "1_1") (pintype "passive"))
      (node (ref "R58") (pin "1") (pinfunction "1_1") (pintype "passive"))
      (node (ref "R6") (pin "2") (pinfunction "2_2") (pintype "passive"))
      (node (ref "SD1") (pin "6") (pinfunction "VSS_6") (pintype "bidirectional"))
      (node (ref "SD1") (pin "G1") (pinfunction "G1_G1") (pintype "bidirectional"))
      (node (ref "SD1") (pin "G2") (pinfunction "G2_G2") (pintype "bidirectional"))
      (node (ref "SD1") (pin "G3") (pinfunction "G3_G3") (pintype "bidirectional"))
      (node (ref "SD1") (pin "G4") (pinfunction "G4_G4") (pintype "bidirectional"))
      (node (ref "U1") (pin "2") (pinfunction "GND_2") (pintype "bidirectional"))
      (node (ref "U11") (pin "7") (pinfunction "GND_7") (pintype "bidirectional"))
      (node (ref "U2") (pin "1") (pinfunction "GND1_1") (pintype "bidirectional"))
      (node (ref "U2") (pin "40") (pinfunction "GND2_40") (pintype "bidirectional"))
      (node (ref "U2") (pin "41") (pinfunction "GND3_41") (pintype "bidirectional"))
      (node (ref "U2") (pin "42") (pinfunction "GND4_42") (pintype "bidirectional"))
      (node (ref "U2") (pin "43") (pinfunction "GND5_43") (pintype "bidirectional"))
      (node (ref "U2") (pin "44") (pinfunction "GND6_44") (pintype "bidirectional"))
      (node (ref "U2") (pin "45") (pinfunction "GND7_45") (pintype "bidirectional"))
      (node (ref "U2") (pin "46") (pinfunction "GND8_46") (pintype "bidirectional"))
      (node (ref "U2") (pin "47") (pinfunction "GND9_47") (pintype "bidirectional"))
      (node (ref "U2") (pin "48") (pinfunction "GND10_48") (pintype "bidirectional"))
      (node (ref "U2") (pin "49") (pinfunction "GND11_49") (pintype "bidirectional"))
      (node (ref "U26") (pin "2") (pinfunction "GND_2") (pintype "bidirectional"))
      (node (ref "U4") (pin "2") (pinfunction "2-GND_2") (pintype "bidirectional"))
      (node (ref "U6") (pin "1") (pinfunction "GND_1") (pintype "bidirectional"))
    )
    (net (code "62") (name "Net-(C14-Pad1)") (class "Default")
      (node (ref "C14") (pin "1") (pinfunction "1_1") (pintype "passive"))
      (node (ref "C28") (pin "1") (pinfunction "1_1") (pintype "passive"))
      (node (ref "J5") (pin "P$2") (pinfunction "P$2_P$2") (pintype "bidirectional"))
    )
    (net (code "63") (name "Net-(C16-Pad1)") (class "Default")
      (node (ref "C16") (pin "1") (pinfunction "1_1") (pintype "passive"))
      (node (ref "C27") (pin "1") (pinfunction "1_1") (pintype "passive"))
      (node (ref "J5") (pin "P$1") (pinfunction "P$1_P$1") (pintype "bidirectional"))
    )
    (net (code "64") (name "Net-(D6-+)") (class "Default")
      (node (ref "D6") (pin "1") (pinfunction "+_1") (pintype "passive"))
      (node (ref "L5") (pin "2") (pinfunction "2_2") (pintype "bidirectional"))
      (node (ref "U4") (pin "1") (pinfunction "1-SW_1") (pintype "bidirectional"))
    )
    (net (code "65") (name "Net-(J3-CC1)") (class "Default")
      (node (ref "J3") (pin "A5") (pinfunction "CC1_A5") (pintype "bidirectional"))
      (node (ref "R13") (pin "2") (pinfunction "2_2") (pintype "passive"))
    )
    (net (code "66") (name "Net-(J3-CC2)") (class "Default")
      (node (ref "J3") (pin "B5") (pinfunction "CC2_B5") (pintype "bidirectional"))
      (node (ref "R14") (pin "1") (pinfunction "1_1") (pintype "passive"))
    )
    (net (code "67") (name "Net-(JP1-DISP)") (class "Default")
      (node (ref "JP1") (pin "P$10") (pinfunction "DISP_P$10") (pintype "bidirectional"))
      (node (ref "R25") (pin "2") (pinfunction "2_2") (pintype "passive"))
    )
    (net (code "68") (name "Net-(L4-P$1)") (class "Default")
      (node (ref "L4") (pin "1") (pinfunction "P$1_1") (pintype "bidirectional"))
      (node (ref "U1") (pin "3") (pinfunction "SW_3") (pintype "bidirectional"))
    )
    (net (code "69") (name "Net-(LED1-Pad+)") (class "Default")
      (node (ref "LED1") (pin "+") (pinfunction "+_+") (pintype "passive"))
      (node (ref "R3") (pin "1") (pinfunction "1_1") (pintype "passive"))
    )
    (net (code "70") (name "Net-(Q3-G)") (class "Default")
      (node (ref "Q3") (pin "1") (pinfunction "G_1") (pintype "bidirectional"))
      (node (ref "R2") (pin "1") (pinfunction "1_1") (pintype "passive"))
      (node (ref "R44") (pin "2") (pinfunction "2_2") (pintype "passive"))
    )
    (net (code "71") (name "Net-(Q4-G)") (class "Default")
      (node (ref "Q4") (pin "1") (pinfunction "G_1") (pintype "bidirectional"))
      (node (ref "Q6") (pin "3") (pinfunction "C_3") (pintype "passive"))
      (node (ref "R48") (pin "2") (pinfunction "2_2") (pintype "passive"))
    )
    (net (code "72") (name "Net-(Q5-B)") (class "Default")
      (node (ref "Q5") (pin "1") (pinfunction "B_1") (pintype "passive"))
      (node (ref "R11") (pin "1") (pinfunction "1_1") (pintype "passive"))
      (node (ref "R58") (pin "2") (pinfunction "2_2") (pintype "passive"))
    )
    (net (code "73") (name "Net-(Q6-B)") (class "Default")
      (node (ref "Q6") (pin "1") (pinfunction "B_1") (pintype "passive"))
      (node (ref "R54") (pin "1") (pinfunction "1_1") (pintype "passive"))
      (node (ref "R55") (pin "2") (pinfunction "2_2") (pintype "passive"))
    )
    (net (code "74") (name "Net-(Q9-B)") (class "Default")
      (node (ref "Q9") (pin "1") (pinfunction "B_1") (pintype "passive"))
      (node (ref "R75") (pin "1") (pinfunction "1_1") (pintype "passive"))
    )
    (net (code "75") (name "Net-(Q10-B)") (class "Default")
      (node (ref "Q10") (pin "1") (pinfunction "B_1") (pintype "passive"))
      (node (ref "R74") (pin "1") (pinfunction "1_1") (pintype "passive"))
    )
    (net (code "76") (name "Net-(Q30-G)") (class "Default")
      (node (ref "Q30") (pin "1") (pinfunction "G_1") (pintype "bidirectional"))
      (node (ref "Q5") (pin "3") (pinfunction "C_3") (pintype "passive"))
      (node (ref "R172") (pin "2") (pinfunction "2_2") (pintype "passive"))
    )
    (net (code "77") (name "Net-(SD1-DATA1)") (class "Default")
      (node (ref "R17") (pin "2") (pinfunction "2_2") (pintype "passive"))
      (node (ref "SD1") (pin "8") (pinfunction "DATA1_8") (pintype "bidirectional"))
    )
    (net (code "78") (name "Net-(SD1-DATA2)") (class "Default")
      (node (ref "R16") (pin "2") (pinfunction "2_2") (pintype "passive"))
      (node (ref "SD1") (pin "1") (pinfunction "DATA2_1") (pintype "bidirectional"))
    )
    (net (code "79") (name "Net-(U1-FB)") (class "Default")
      (node (ref "R20") (pin "2") (pinfunction "2_2") (pintype "passive"))
      (node (ref "R21") (pin "1") (pinfunction "1_1") (pintype "passive"))
      (node (ref "U1") (pin "5") (pinfunction "FB_5") (pintype "bidirectional"))
    )
    (net (code "80") (name "Net-(U6-RXD)") (class "Default")
      (node (ref "R71") (pin "2") (pinfunction "2_2") (pintype "passive"))
      (node (ref "U6") (pin "3") (pinfunction "RXD_3") (pintype "bidirectional"))
    )
    (net (code "81") (name "Net-(U6-TXD)") (class "Default")
      (node (ref "R72") (pin "2") (pinfunction "2_2") (pintype "passive"))
      (node (ref "U6") (pin "2") (pinfunction "TXD_2") (pintype "bidirectional"))
    )
    (net (code "82") (name "Net-(U11-VON)") (class "Default")
      (node (ref "C27") (pin "2") (pinfunction "2_2") (pintype "passive"))
      (node (ref "U11") (pin "5") (pinfunction "VON_5") (pintype "bidirectional"))
    )
    (net (code "83") (name "Net-(U11-VOP)") (class "Default")
      (node (ref "C28") (pin "2") (pinfunction "2_2") (pintype "passive"))
      (node (ref "U11") (pin "8") (pinfunction "VOP_8") (pintype "bidirectional"))
    )
    (net (code "84") (name "Net-(U26-PROG)") (class "Default")
      (node (ref "R6") (pin "1") (pinfunction "1_1") (pintype "passive"))
      (node (ref "U26") (pin "5") (pinfunction "PROG_5") (pintype "bidirectional"))
    )
    (net (code "85") (name "unconnected-(J2-Pad2)") (class "Default")
      (node (ref "J2") (pin "2") (pinfunction "2_2") (pintype "bidirectional"))
    )
    (net (code "86") (name "unconnected-(J3-SBU1-PadA8)") (class "Default")
      (node (ref "J3") (pin "A8") (pinfunction "SBU1_A8") (pintype "bidirectional"))
    )
    (net (code "87") (name "unconnected-(J3-SBU2-PadB8)") (class "Default")
      (node (ref "J3") (pin "B8") (pinfunction "SBU2_B8") (pintype "bidirectional"))
    )
    (net (code "88") (name "unconnected-(J4-P$3-Pad3)") (class "Default")
      (node (ref "J4") (pin "3") (pinfunction "P$3_3") (pintype "bidirectional"))
    )
    (net (code "89") (name "unconnected-(J6-Pad8)") (class "Default")
      (node (ref "J6") (pin "8") (pinfunction "8_8") (pintype "bidirectional"))
    )
    (net (code "90") (name "unconnected-(JP1-NC-PadP$6)") (class "Default")
      (node (ref "JP1") (pin "P$6") (pinfunction "NC_P$6") (pintype "bidirectional"))
    )
    (net (code "91") (name "unconnected-(SD1-CDN-Pad9)") (class "Default")
      (node (ref "SD1") (pin "9") (pinfunction "CDN_9") (pintype "bidirectional"))
    )
    (net (code "92") (name "unconnected-(U2-NC1-Pad28)") (class "Default")
      (node (ref "U2") (pin "28") (pinfunction "NC1_28") (pintype "bidirectional"))
    )
    (net (code "93") (name "unconnected-(U2-NC2-Pad29)") (class "Default")
      (node (ref "U2") (pin "29") (pinfunction "NC2_29") (pintype "bidirectional"))
    )
    (net (code "94") (name "unconnected-(U2-NC3-Pad30)") (class "Default")
      (node (ref "U2") (pin "30") (pinfunction "NC3_30") (pintype "bidirectional"))
    )
    (net (code "95") (name "unconnected-(U6-CTS#-Pad9)") (class "Default")
      (node (ref "U6") (pin "9") (pinfunction "CTS#_9") (pintype "bidirectional"))
    )
    (net (code "96") (name "unconnected-(U6-DCD#-Pad12)") (class "Default")
      (node (ref "U6") (pin "12") (pinfunction "DCD#_12") (pintype "bidirectional"))
    )
    (net (code "97") (name "unconnected-(U6-DSR#-Pad10)") (class "Default")
      (node (ref "U6") (pin "10") (pinfunction "DSR#_10") (pintype "bidirectional"))
    )
    (net (code "98") (name "unconnected-(U6-RI#-Pad11)") (class "Default")
      (node (ref "U6") (pin "11") (pinfunction "RI#_11") (pintype "bidirectional"))
    )
    (net (code "99") (name "unconnected-(U6-RS232-Pad15)") (class "Default")
      (node (ref "U6") (pin "15") (pinfunction "RS232_15") (pintype "bidirectional"))
    )
    (net (code "100") (name "unconnected-(U6-XI-Pad7)") (class "Default")
      (node (ref "U6") (pin "7") (pinfunction "XI_7") (pintype "bidirectional"))
    )
    (net (code "101") (name "unconnected-(U6-XO-Pad8)") (class "Default")
      (node (ref "U6") (pin "8") (pinfunction "XO_8") (pintype "bidirectional"))
    )
    (net (code "102") (name "unconnected-(U11-PE-Pad9)") (class "Default")
      (node (ref "U11") (pin "9") (pinfunction "PE_9") (pintype "bidirectional"))
    )
    (net (code "103") (name "unconnected-(U26-GHRG-Pad1)") (class "Default")
      (node (ref "U26") (pin "1") (pinfunction "GHRG_1") (pintype "bidirectional"))
    )
  )
)
